# Top.net
KiCad netlist of a schematic drawn in Altium Designer
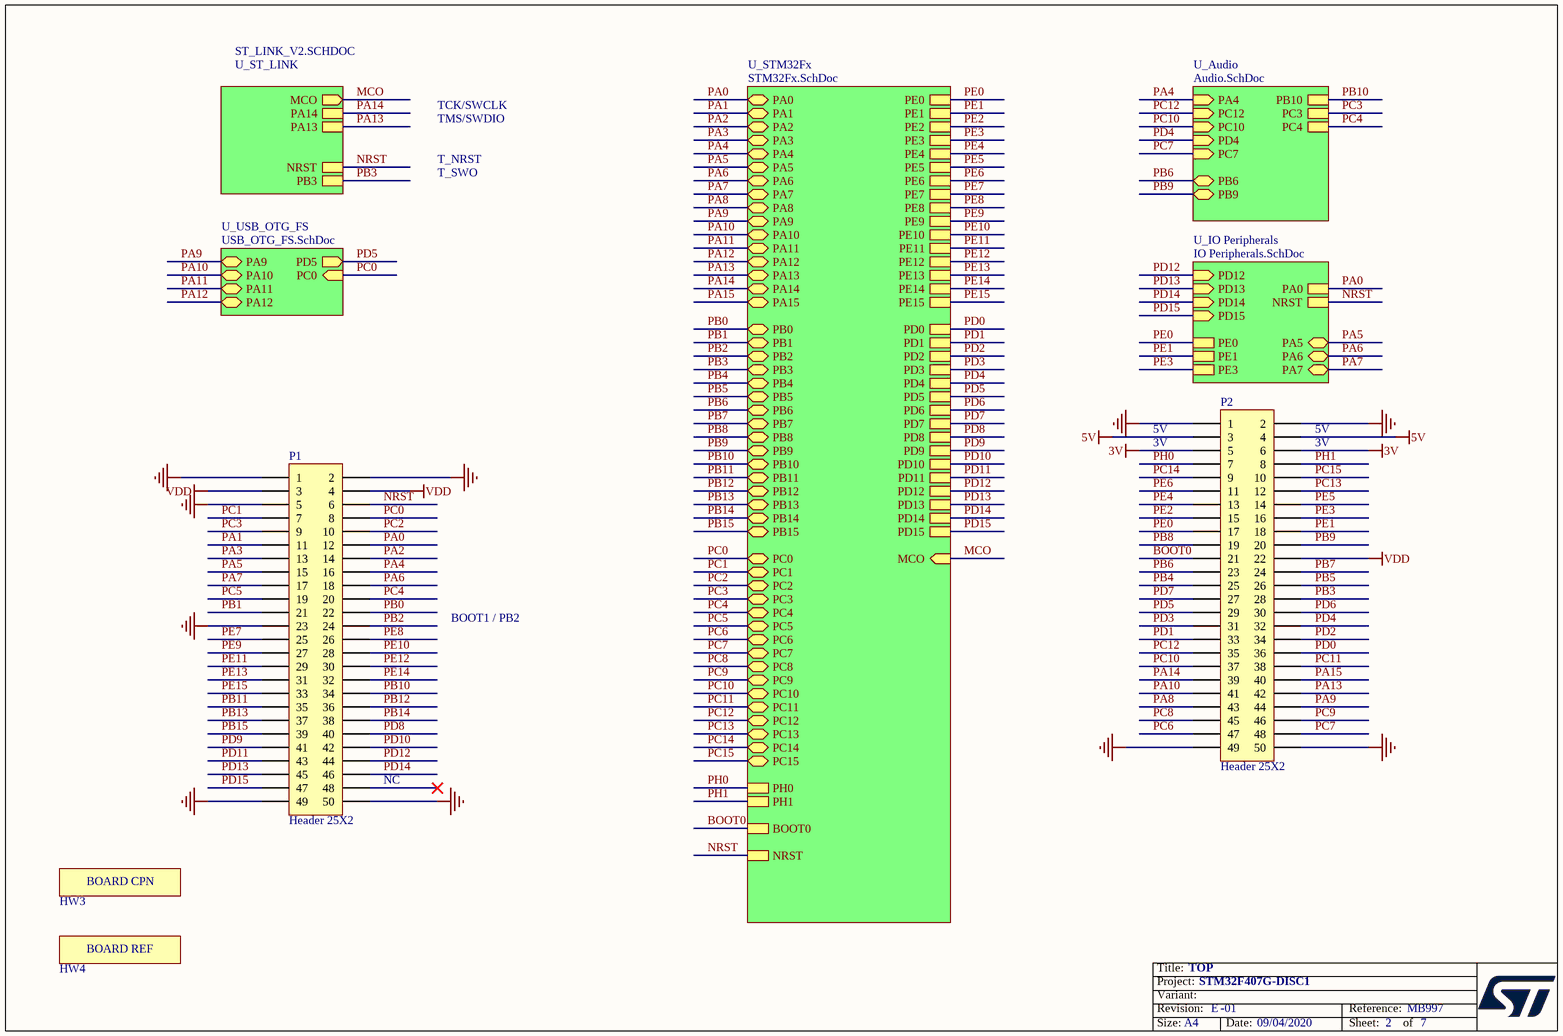
[diagram p0: Top.SchDoc]

(export (version "E")
  (design (tool "Eeschema 10.0.6"))
  (components
    (comp (ref "HW3")
      (value "STICKER_BOARD_CPN")
      (footprint "STICKER_25X9_")
      (libsource (lib "MB997") (part "STICKER_BOARD_CPN"))
    )
    (comp (ref "HW4")
      (value "STICKER_BOARD_REF")
      (footprint "STICKER_25X9_")
      (libsource (lib "MB997") (part "STICKER_BOARD_REF"))
    )
    (comp (ref "P1")
      (value "Header 25X2")
      (footprint "HEAD25X2$2F$2.54")
      (description "Header, 25-Pin, Dual row")
      (fields (field (name "PUBLISHER") "Altium Limited"))
      (libsource (lib "Miscellaneous Connectors") (part "Header 25X2"))
    )
    (comp (ref "P2")
      (value "Header 25X2")
      (footprint "HEAD25X2$2F$2.54")
      (description "Header, 25-Pin, Dual row")
      (fields (field (name "PUBLISHER") "Altium Limited"))
      (libsource (lib "Miscellaneous Connectors") (part "Header 25X2"))
    )
  )
  (nets
    (net (code "1") (name "/BOOT0") (class "Default")
      (node (ref "P2") (pin "21") (pinfunction "21_21") (pintype "passive"))
    )
    (net (code "3") (name "/NRST") (class "Default")
      (node (ref "P1") (pin "6") (pinfunction "6_6") (pintype "passive"))
    )
    (net (code "4") (name "/PA0") (class "Default")
      (node (ref "P1") (pin "12") (pinfunction "12_12") (pintype "passive"))
    )
    (net (code "5") (name "/PA1") (class "Default")
      (node (ref "P1") (pin "11") (pinfunction "11_11") (pintype "passive"))
    )
    (net (code "6") (name "/PA2") (class "Default")
      (node (ref "P1") (pin "14") (pinfunction "14_14") (pintype "passive"))
    )
    (net (code "7") (name "/PA3") (class "Default")
      (node (ref "P1") (pin "13") (pinfunction "13_13") (pintype "passive"))
    )
    (net (code "8") (name "/PA4") (class "Default")
      (node (ref "P1") (pin "16") (pinfunction "16_16") (pintype "passive"))
    )
    (net (code "9") (name "/PA5") (class "Default")
      (node (ref "P1") (pin "15") (pinfunction "15_15") (pintype "passive"))
    )
    (net (code "10") (name "/PA6") (class "Default")
      (node (ref "P1") (pin "18") (pinfunction "18_18") (pintype "passive"))
    )
    (net (code "11") (name "/PA7") (class "Default")
      (node (ref "P1") (pin "17") (pinfunction "17_17") (pintype "passive"))
    )
    (net (code "12") (name "/PA8") (class "Default")
      (node (ref "P2") (pin "43") (pinfunction "43_43") (pintype "passive"))
    )
    (net (code "13") (name "/PA9") (class "Default")
      (node (ref "P2") (pin "44") (pinfunction "44_44") (pintype "passive"))
    )
    (net (code "14") (name "/PA10") (class "Default")
      (node (ref "P2") (pin "41") (pinfunction "41_41") (pintype "passive"))
    )
    (net (code "17") (name "/PA13") (class "Default")
      (node (ref "P2") (pin "42") (pinfunction "42_42") (pintype "passive"))
    )
    (net (code "18") (name "/PA14") (class "Default")
      (node (ref "P2") (pin "39") (pinfunction "39_39") (pintype "passive"))
    )
    (net (code "19") (name "/PA15") (class "Default")
      (node (ref "P2") (pin "40") (pinfunction "40_40") (pintype "passive"))
    )
    (net (code "20") (name "/PB0") (class "Default")
      (node (ref "P1") (pin "22") (pinfunction "22_22") (pintype "passive"))
    )
    (net (code "21") (name "/PB1") (class "Default")
      (node (ref "P1") (pin "21") (pinfunction "21_21") (pintype "passive"))
    )
    (net (code "22") (name "/PB2") (class "Default")
      (node (ref "P1") (pin "24") (pinfunction "24_24") (pintype "passive"))
    )
    (net (code "23") (name "/PB3") (class "Default")
      (node (ref "P2") (pin "28") (pinfunction "28_28") (pintype "passive"))
    )
    (net (code "24") (name "/PB4") (class "Default")
      (node (ref "P2") (pin "25") (pinfunction "25_25") (pintype "passive"))
    )
    (net (code "25") (name "/PB5") (class "Default")
      (node (ref "P2") (pin "26") (pinfunction "26_26") (pintype "passive"))
    )
    (net (code "26") (name "/PB6") (class "Default")
      (node (ref "P2") (pin "23") (pinfunction "23_23") (pintype "passive"))
    )
    (net (code "27") (name "/PB7") (class "Default")
      (node (ref "P2") (pin "24") (pinfunction "24_24") (pintype "passive"))
    )
    (net (code "28") (name "/PB8") (class "Default")
      (node (ref "P2") (pin "19") (pinfunction "19_19") (pintype "passive"))
    )
    (net (code "29") (name "/PB9") (class "Default")
      (node (ref "P2") (pin "20") (pinfunction "20_20") (pintype "passive"))
    )
    (net (code "30") (name "/PB10") (class "Default")
      (node (ref "P1") (pin "34") (pinfunction "34_34") (pintype "passive"))
    )
    (net (code "31") (name "/PB11") (class "Default")
      (node (ref "P1") (pin "35") (pinfunction "35_35") (pintype "passive"))
    )
    (net (code "32") (name "/PB12") (class "Default")
      (node (ref "P1") (pin "36") (pinfunction "36_36") (pintype "passive"))
    )
    (net (code "33") (name "/PB13") (class "Default")
      (node (ref "P1") (pin "37") (pinfunction "37_37") (pintype "passive"))
    )
    (net (code "34") (name "/PB14") (class "Default")
      (node (ref "P1") (pin "38") (pinfunction "38_38") (pintype "passive"))
    )
    (net (code "35") (name "/PB15") (class "Default")
      (node (ref "P1") (pin "39") (pinfunction "39_39") (pintype "passive"))
    )
    (net (code "36") (name "/PC0") (class "Default")
      (node (ref "P1") (pin "8") (pinfunction "8_8") (pintype "passive"))
    )
    (net (code "37") (name "/PC1") (class "Default")
      (node (ref "P1") (pin "7") (pinfunction "7_7") (pintype "passive"))
    )
    (net (code "38") (name "/PC2") (class "Default")
      (node (ref "P1") (pin "10") (pinfunction "10_10") (pintype "passive"))
    )
    (net (code "39") (name "/PC3") (class "Default")
      (node (ref "P1") (pin "9") (pinfunction "9_9") (pintype "passive"))
    )
    (net (code "40") (name "/PC4") (class "Default")
      (node (ref "P1") (pin "20") (pinfunction "20_20") (pintype "passive"))
    )
    (net (code "41") (name "/PC5") (class "Default")
      (node (ref "P1") (pin "19") (pinfunction "19_19") (pintype "passive"))
    )
    (net (code "42") (name "/PC6") (class "Default")
      (node (ref "P2") (pin "47") (pinfunction "47_47") (pintype "passive"))
    )
    (net (code "43") (name "/PC7") (class "Default")
      (node (ref "P2") (pin "48") (pinfunction "48_48") (pintype "passive"))
    )
    (net (code "44") (name "/PC8") (class "Default")
      (node (ref "P2") (pin "45") (pinfunction "45_45") (pintype "passive"))
    )
    (net (code "45") (name "/PC9") (class "Default")
      (node (ref "P2") (pin "46") (pinfunction "46_46") (pintype "passive"))
    )
    (net (code "46") (name "/PC10") (class "Default")
      (node (ref "P2") (pin "37") (pinfunction "37_37") (pintype "passive"))
    )
    (net (code "47") (name "/PC11") (class "Default")
      (node (ref "P2") (pin "38") (pinfunction "38_38") (pintype "passive"))
    )
    (net (code "48") (name "/PC12") (class "Default")
      (node (ref "P2") (pin "35") (pinfunction "35_35") (pintype "passive"))
    )
    (net (code "49") (name "/PC13") (class "Default")
      (node (ref "P2") (pin "12") (pinfunction "12_12") (pintype "passive"))
    )
    (net (code "50") (name "/PC14") (class "Default")
      (node (ref "P2") (pin "9") (pinfunction "9_9") (pintype "passive"))
    )
    (net (code "51") (name "/PC15") (class "Default")
      (node (ref "P2") (pin "10") (pinfunction "10_10") (pintype "passive"))
    )
    (net (code "52") (name "/PD0") (class "Default")
      (node (ref "P2") (pin "36") (pinfunction "36_36") (pintype "passive"))
    )
    (net (code "53") (name "/PD1") (class "Default")
      (node (ref "P2") (pin "33") (pinfunction "33_33") (pintype "passive"))
    )
    (net (code "54") (name "/PD2") (class "Default")
      (node (ref "P2") (pin "34") (pinfunction "34_34") (pintype "passive"))
    )
    (net (code "55") (name "/PD3") (class "Default")
      (node (ref "P2") (pin "31") (pinfunction "31_31") (pintype "passive"))
    )
    (net (code "56") (name "/PD4") (class "Default")
      (node (ref "P2") (pin "32") (pinfunction "32_32") (pintype "passive"))
    )
    (net (code "57") (name "/PD5") (class "Default")
      (node (ref "P2") (pin "29") (pinfunction "29_29") (pintype "passive"))
    )
    (net (code "58") (name "/PD6") (class "Default")
      (node (ref "P2") (pin "30") (pinfunction "30_30") (pintype "passive"))
    )
    (net (code "59") (name "/PD7") (class "Default")
      (node (ref "P2") (pin "27") (pinfunction "27_27") (pintype "passive"))
    )
    (net (code "60") (name "/PD8") (class "Default")
      (node (ref "P1") (pin "40") (pinfunction "40_40") (pintype "passive"))
    )
    (net (code "61") (name "/PD9") (class "Default")
      (node (ref "P1") (pin "41") (pinfunction "41_41") (pintype "passive"))
    )
    (net (code "62") (name "/PD10") (class "Default")
      (node (ref "P1") (pin "42") (pinfunction "42_42") (pintype "passive"))
    )
    (net (code "63") (name "/PD11") (class "Default")
      (node (ref "P1") (pin "43") (pinfunction "43_43") (pintype "passive"))
    )
    (net (code "64") (name "/PD12") (class "Default")
      (node (ref "P1") (pin "44") (pinfunction "44_44") (pintype "passive"))
    )
    (net (code "65") (name "/PD13") (class "Default")
      (node (ref "P1") (pin "45") (pinfunction "45_45") (pintype "passive"))
    )
    (net (code "66") (name "/PD14") (class "Default")
      (node (ref "P1") (pin "46") (pinfunction "46_46") (pintype "passive"))
    )
    (net (code "67") (name "/PD15") (class "Default")
      (node (ref "P1") (pin "47") (pinfunction "47_47") (pintype "passive"))
    )
    (net (code "68") (name "/PE0") (class "Default")
      (node (ref "P2") (pin "17") (pinfunction "17_17") (pintype "passive"))
    )
    (net (code "69") (name "/PE1") (class "Default")
      (node (ref "P2") (pin "18") (pinfunction "18_18") (pintype "passive"))
    )
    (net (code "70") (name "/PE2") (class "Default")
      (node (ref "P2") (pin "15") (pinfunction "15_15") (pintype "passive"))
    )
    (net (code "71") (name "/PE3") (class "Default")
      (node (ref "P2") (pin "16") (pinfunction "16_16") (pintype "passive"))
    )
    (net (code "72") (name "/PE4") (class "Default")
      (node (ref "P2") (pin "13") (pinfunction "13_13") (pintype "passive"))
    )
    (net (code "73") (name "/PE5") (class "Default")
      (node (ref "P2") (pin "14") (pinfunction "14_14") (pintype "passive"))
    )
    (net (code "74") (name "/PE6") (class "Default")
      (node (ref "P2") (pin "11") (pinfunction "11_11") (pintype "passive"))
    )
    (net (code "75") (name "/PE7") (class "Default")
      (node (ref "P1") (pin "25") (pinfunction "25_25") (pintype "passive"))
    )
    (net (code "76") (name "/PE8") (class "Default")
      (node (ref "P1") (pin "26") (pinfunction "26_26") (pintype "passive"))
    )
    (net (code "77") (name "/PE9") (class "Default")
      (node (ref "P1") (pin "27") (pinfunction "27_27") (pintype "passive"))
    )
    (net (code "78") (name "/PE10") (class "Default")
      (node (ref "P1") (pin "28") (pinfunction "28_28") (pintype "passive"))
    )
    (net (code "79") (name "/PE11") (class "Default")
      (node (ref "P1") (pin "29") (pinfunction "29_29") (pintype "passive"))
    )
    (net (code "80") (name "/PE12") (class "Default")
      (node (ref "P1") (pin "30") (pinfunction "30_30") (pintype "passive"))
    )
    (net (code "81") (name "/PE13") (class "Default")
      (node (ref "P1") (pin "31") (pinfunction "31_31") (pintype "passive"))
    )
    (net (code "82") (name "/PE14") (class "Default")
      (node (ref "P1") (pin "32") (pinfunction "32_32") (pintype "passive"))
    )
    (net (code "83") (name "/PE15") (class "Default")
      (node (ref "P1") (pin "33") (pinfunction "33_33") (pintype "passive"))
    )
    (net (code "84") (name "/PH0") (class "Default")
      (node (ref "P2") (pin "7") (pinfunction "7_7") (pintype "passive"))
    )
    (net (code "85") (name "/PH1") (class "Default")
      (node (ref "P2") (pin "8") (pinfunction "8_8") (pintype "passive"))
    )
    (net (code "86") (name "3V") (class "Default")
      (node (ref "P2") (pin "5") (pinfunction "5_5") (pintype "passive"))
      (node (ref "P2") (pin "6") (pinfunction "6_6") (pintype "passive"))
    )
    (net (code "87") (name "5V") (class "Default")
      (node (ref "P2") (pin "3") (pinfunction "3_3") (pintype "passive"))
      (node (ref "P2") (pin "4") (pinfunction "4_4") (pintype "passive"))
    )
    (net (code "88") (name "GND") (class "Default")
      (node (ref "P1") (pin "1") (pinfunction "1_1") (pintype "passive"))
      (node (ref "P1") (pin "2") (pinfunction "2_2") (pintype "passive"))
      (node (ref "P1") (pin "23") (pinfunction "23_23") (pintype "passive"))
      (node (ref "P1") (pin "49") (pinfunction "49_49") (pintype "passive"))
      (node (ref "P1") (pin "5") (pinfunction "5_5") (pintype "passive"))
      (node (ref "P1") (pin "50") (pinfunction "50_50") (pintype "passive"))
      (node (ref "P2") (pin "1") (pinfunction "1_1") (pintype "passive"))
      (node (ref "P2") (pin "2") (pinfunction "2_2") (pintype "passive"))
      (node (ref "P2") (pin "49") (pinfunction "49_49") (pintype "passive"))
      (node (ref "P2") (pin "50") (pinfunction "50_50") (pintype "passive"))
    )
    (net (code "89") (name "VDD") (class "Default")
      (node (ref "P1") (pin "3") (pinfunction "3_3") (pintype "passive"))
      (node (ref "P1") (pin "4") (pinfunction "4_4") (pintype "passive"))
      (node (ref "P2") (pin "22") (pinfunction "22_22") (pintype "passive"))
    )
    (net (code "90") (name "unconnected-(P1-Pad48)") (class "Default")
      (node (ref "P1") (pin "48") (pinfunction "48_48") (pintype "passive+no_connect"))
    )
  )
)
